# SLAYER_PyroActuation.net
KiCad netlist of a schematic drawn in Altium Designer
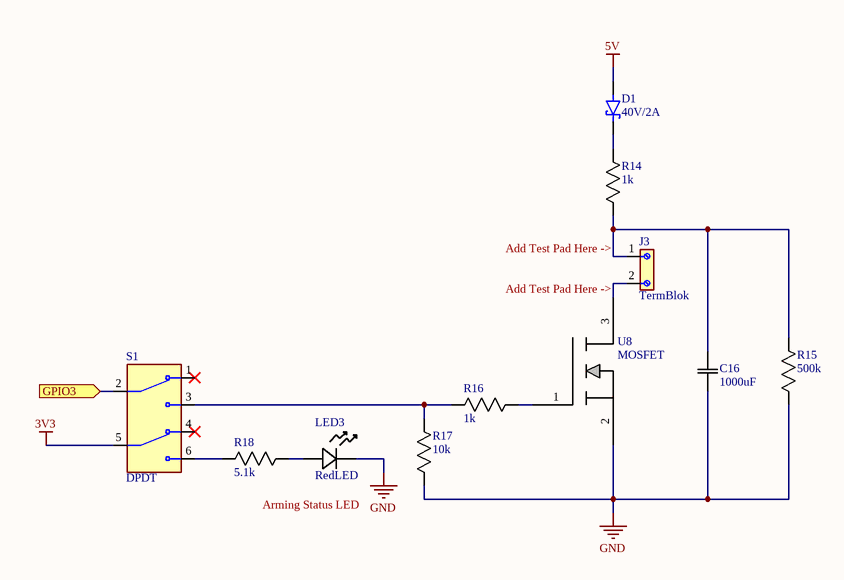
[diagram p0: SLAYER_PyroActuation.SchDoc]

(export (version "E")
  (design (tool "Eeschema 10.0.6"))
  (components
    (comp (ref "C16")
      (value "1000uF")
      (footprint "1000uF/16V")
      (description "A768MS108M1CLAS015")
      (fields (field (name "COPYRIGHT") "Copyright (C) 2025 Ultra Librarian. All rights reserved."))
      (libsource (lib "SLAYER_Altium_Sch") (part "1000uF/16V"))
    )
    (comp (ref "D1")
      (value "40V/2A")
      (footprint "Schotty/40V/2A")
      (description "SS24")
      (fields (field (name "MF") "Taiwan Semiconductor"))
      (libsource (lib "SLAYER_Altium_Sch") (part "Schottky/40V/2A"))
    )
    (comp (ref "J3")
      (value "TermBlok")
      (footprint "TerminalBlock")
      (description "691137710002")
      (fields (field (name "MF") "WÃ¼rth Elektronik"))
      (libsource (lib "SLAYER_Altium_Sch") (part "2TerminalBlock"))
    )
    (comp (ref "LED3")
      (value "RedLED")
      (footprint "RedLED")
      (description "LTST-C190KRKT")
      (fields (field (name "COPYRIGHT") "Copyright (C) 2026 Ultra Librarian. All rights reserved."))
      (libsource (lib "SLAYER_Altium_Sch") (part "RedLED"))
    )
    (comp (ref "R14")
      (value "1k")
      (footprint "1k/0.125W")
      (description "CRCW06031K00FKEA")
      (fields (field (name "COPYRIGHT") "Copyright (C) 2026 Ultra Librarian. All rights reserved."))
      (libsource (lib "SLAYER_Altium_Sch") (part "1k/0.125W"))
    )
    (comp (ref "R15")
      (value "500k")
      (footprint "500k/0.25W")
      (description "RC1206FR-07470KL")
      (fields (field (name "COPYRIGHT") "Copyright (C) 2026 Ultra Librarian. All rights reserved."))
      (libsource (lib "SLAYER_Altium_Sch") (part "500k/0.25W"))
    )
    (comp (ref "R16")
      (value "1k")
      (footprint "1k/0.125W")
      (description "CRCW06031K00FKEA")
      (fields (field (name "COPYRIGHT") "Copyright (C) 2026 Ultra Librarian. All rights reserved."))
      (libsource (lib "SLAYER_Altium_Sch") (part "1k/0.125W"))
    )
    (comp (ref "R17")
      (value "10k")
      (footprint "10k/0.125W")
      (description "CRCW060310K0FKEA")
      (fields (field (name "COPYRIGHT") "Copyright (C) 2025 Ultra Librarian. All rights reserved."))
      (libsource (lib "SLAYER_Altium_Sch") (part "10k/0.125W"))
    )
    (comp (ref "R18")
      (value "5.1k")
      (footprint "5.1k/0.25W")
      (description "CRCW08055K10FKEA")
      (fields (field (name "COPYRIGHT") "Copyright (C) 2026 Ultra Librarian. All rights reserved."))
      (libsource (lib "SLAYER_Altium_Sch") (part "5.1k/0.25W"))
    )
    (comp (ref "S1")
      (value "DPDT")
      (footprint "SlideSwitch2")
      (description "GF-126-0159")
      (fields (field (name "MF") "{'manufacturer': u'CW Industries'}"))
      (libsource (lib "SLAYER_Altium_Sch") (part "SlideSwitch"))
    )
    (comp (ref "U8")
      (value "MOSFET")
      (footprint "MOSFET")
      (description "AO3400A")
      (fields (field (name "COPYRIGHT") "Copyright (C) 2025 Ultra Librarian. All rights reserved."))
      (libsource (lib "SLAYER_Altium_Sch") (part "AO3400A"))
    )
  )
  (nets
    (net (code "1") (name "/GPIO3") (class "Default")
      (node (ref "S1") (pin "2") (pinfunction "COM1_2") (pintype "passive"))
    )
    (net (code "2") (name "3V3") (class "Default")
      (node (ref "S1") (pin "5") (pinfunction "COM2_5") (pintype "passive"))
    )
    (net (code "3") (name "5V") (class "Default")
      (node (ref "D1") (pin "A") (pinfunction "A_A") (pintype "passive"))
    )
    (net (code "4") (name "GND") (class "Default")
      (node (ref "C16") (pin "1") (pinfunction "1_1") (pintype "passive"))
      (node (ref "LED3") (pin "1") (pinfunction "CATHODE_1") (pintype "passive"))
      (node (ref "R15") (pin "2") (pinfunction "2_2") (pintype "passive"))
      (node (ref "R17") (pin "2") (pinfunction "2_2") (pintype "passive"))
      (node (ref "U8") (pin "2") (pinfunction "S_2") (pintype "passive"))
    )
    (net (code "5") (name "Net-(C16-Pad2)") (class "Default")
      (node (ref "C16") (pin "2") (pinfunction "2_2") (pintype "passive"))
      (node (ref "J3") (pin "1") (pinfunction "1_1") (pintype "passive"))
      (node (ref "R14") (pin "2") (pinfunction "2_2") (pintype "passive"))
      (node (ref "R15") (pin "1") (pinfunction "1_1") (pintype "passive"))
    )
    (net (code "6") (name "Net-(D1-K)") (class "Default")
      (node (ref "D1") (pin "C") (pinfunction "K_C") (pintype "passive"))
      (node (ref "R14") (pin "1") (pinfunction "1_1") (pintype "passive"))
    )
    (net (code "7") (name "Net-(LED3-ANODE)") (class "Default")
      (node (ref "LED3") (pin "2") (pinfunction "ANODE_2") (pintype "passive"))
      (node (ref "R18") (pin "2") (pinfunction "2_2") (pintype "passive"))
    )
    (net (code "8") (name "Net-(S1-NO1)") (class "Default")
      (node (ref "R16") (pin "2") (pinfunction "2_2") (pintype "passive"))
      (node (ref "R17") (pin "1") (pinfunction "1_1") (pintype "passive"))
      (node (ref "S1") (pin "3") (pinfunction "NO1_3") (pintype "passive"))
    )
    (net (code "9") (name "Net-(S1-NO2)") (class "Default")
      (node (ref "R18") (pin "1") (pinfunction "1_1") (pintype "passive"))
      (node (ref "S1") (pin "6") (pinfunction "NO2_6") (pintype "passive"))
    )
    (net (code "10") (name "Net-(U8-D)") (class "Default")
      (node (ref "J3") (pin "2") (pinfunction "2_2") (pintype "passive"))
      (node (ref "U8") (pin "3") (pinfunction "D_3") (pintype "passive"))
    )
    (net (code "11") (name "Net-(U8-G)") (class "Default")
      (node (ref "R16") (pin "1") (pinfunction "1_1") (pintype "passive"))
      (node (ref "U8") (pin "1") (pinfunction "G_1") (pintype "passive"))
    )
    (net (code "12") (name "unconnected-(S1-NC1-Pad1)") (class "Default")
      (node (ref "S1") (pin "1") (pinfunction "NC1_1") (pintype "passive+no_connect"))
    )
    (net (code "13") (name "unconnected-(S1-NC2-Pad4)") (class "Default")
      (node (ref "S1") (pin "4") (pinfunction "NC2_4") (pintype "passive+no_connect"))
    )
  )
)
